# Top.net
KiCad netlist of a schematic drawn in Altium Designer
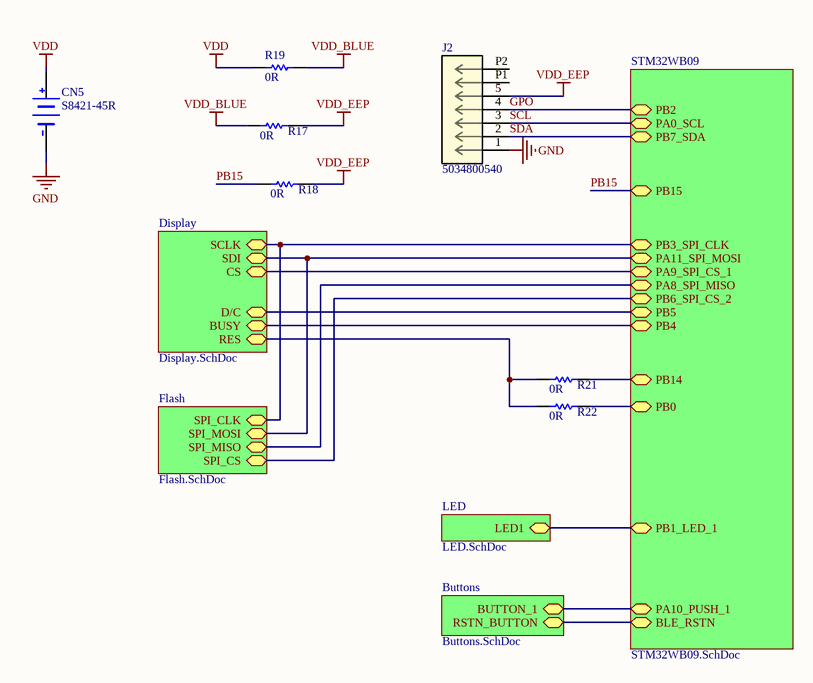
[diagram p0: Top.SchDoc]

(export (version "E")
  (design (tool "Eeschema 10.0.6"))
  (components
    (comp (ref "CN5")
      (value "S8421-45R")
      (footprint "BAT_HARWIN_S8421-45R_CR2032_SMD_2P")
      (description "CR2032 compact battery holder")
      (fields (field (name "INTERNAL_PART_NUMBER") "MCD-02936") (field (name "MANUFACTURER") "HARWIN"))
      (libsource (lib "STEVAL-ESLBLECB") (part "BATTERY HOLDER"))
    )
    (comp (ref "J2")
      (value "5034800540")
      (footprint "CON_5034800540_MOL")
      (description "FFC/FPC Connector, 0.50mm Pitch, Dual Contact, 1.00mm Height, 5 Circuits, Gold over Nickel Plating")
      (fields
        (field (name "MANUFACTURER") "Molex")
        (field (name "COPYRIGHT") "Copyright (C) 2023 Ultra Librarian. All rights reserved.")
      )
      (libsource (lib "STEVAL-ESLBLECB") (part "5034800540_5_circuits"))
    )
    (comp (ref "R17")
      (value "0R")
      (footprint "R0402")
      (description "Resistor, 0R, 0402, +/-5%, 1/16W")
      (fields (field (name "INTERNAL_PART_NUMBER") "MCD-00052") (field (name "MANUFACTURER") "YAGEO"))
      (libsource (lib "STEVAL-ESLBLECB") (part "Resistor"))
    )
    (comp (ref "R18")
      (value "0R")
      (footprint "R0402")
      (description "Resistor, 0R, 0402, +/-5%, 1/16W")
      (fields (field (name "INTERNAL_PART_NUMBER") "MCD-00052") (field (name "MANUFACTURER") "YAGEO"))
      (libsource (lib "STEVAL-ESLBLECB") (part "Resistor"))
    )
    (comp (ref "R19")
      (value "0R")
      (footprint "R0603")
      (description "Resistor, 0R, 0603, +/- 0.5mR, 1/4W")
      (fields
        (field (name "INTERNAL_PART_NUMBER") "MCD-00181")
        (field (name "MANUFACTURER") "ROHM SEMICONDUCTOR")
      )
      (libsource (lib "STEVAL-ESLBLECB") (part "Resistor"))
    )
    (comp (ref "R21")
      (value "0R")
      (footprint "R0402")
      (description "Resistor, 0R, 0402, +/-5%, 1/16W")
      (fields (field (name "INTERNAL_PART_NUMBER") "MCD-00052") (field (name "MANUFACTURER") "YAGEO"))
      (libsource (lib "STEVAL-ESLBLECB") (part "Resistor"))
    )
    (comp (ref "R22")
      (value "0R")
      (footprint "R0402")
      (description "Resistor, 0R, 0402, +/-5%, 1/16W")
      (fields (field (name "INTERNAL_PART_NUMBER") "MCD-00052") (field (name "MANUFACTURER") "YAGEO"))
      (libsource (lib "STEVAL-ESLBLECB") (part "Resistor"))
    )
  )
  (nets
    (net (code "6") (name "/GPO") (class "Default")
      (node (ref "J2") (pin "4") (pinfunction "4_4") (pintype "passive"))
    )
    (net (code "10") (name "/PB0") (class "Default")
      (node (ref "R22") (pin "2") (pinfunction "2_2") (pintype "passive"))
    )
    (net (code "13") (name "/PB14") (class "Default")
      (node (ref "R21") (pin "2") (pinfunction "2_2") (pintype "passive"))
    )
    (net (code "14") (name "/PB15") (class "Default")
      (node (ref "R18") (pin "1") (pinfunction "1_1") (pintype "passive"))
    )
    (net (code "15") (name "/RES") (class "Default")
      (node (ref "R21") (pin "1") (pinfunction "1_1") (pintype "passive"))
      (node (ref "R22") (pin "1") (pinfunction "1_1") (pintype "passive"))
    )
    (net (code "16") (name "/SCL") (class "Default")
      (node (ref "J2") (pin "3") (pinfunction "3_3") (pintype "passive"))
    )
    (net (code "17") (name "/SDA") (class "Default")
      (node (ref "J2") (pin "2") (pinfunction "2_2") (pintype "passive"))
    )
    (net (code "18") (name "GND") (class "Default")
      (node (ref "CN5") (pin "2") (pinfunction "-_2") (pintype "passive"))
      (node (ref "J2") (pin "1") (pinfunction "1_1") (pintype "passive"))
    )
    (net (code "19") (name "VDD") (class "Default")
      (node (ref "CN5") (pin "1") (pinfunction "+_1") (pintype "passive"))
      (node (ref "R19") (pin "1") (pinfunction "1_1") (pintype "passive"))
    )
    (net (code "20") (name "VDD_BLUE") (class "Default")
      (node (ref "R17") (pin "1") (pinfunction "1_1") (pintype "passive"))
      (node (ref "R19") (pin "2") (pinfunction "2_2") (pintype "passive"))
    )
    (net (code "21") (name "VDD_EEP") (class "Default")
      (node (ref "J2") (pin "5") (pinfunction "5_5") (pintype "passive"))
      (node (ref "R17") (pin "2") (pinfunction "2_2") (pintype "passive"))
      (node (ref "R18") (pin "2") (pinfunction "2_2") (pintype "passive"))
    )
    (net (code "22") (name "unconnected-(J2-PadP1)") (class "Default")
      (node (ref "J2") (pin "P1") (pinfunction "P1_P1") (pintype "passive"))
    )
    (net (code "23") (name "unconnected-(J2-PadP2)") (class "Default")
      (node (ref "J2") (pin "P2") (pinfunction "P2_P2") (pintype "passive"))
    )
  )
)
